# BluetoothModulePCB.net
KiCad netlist of a schematic drawn in EAGLE
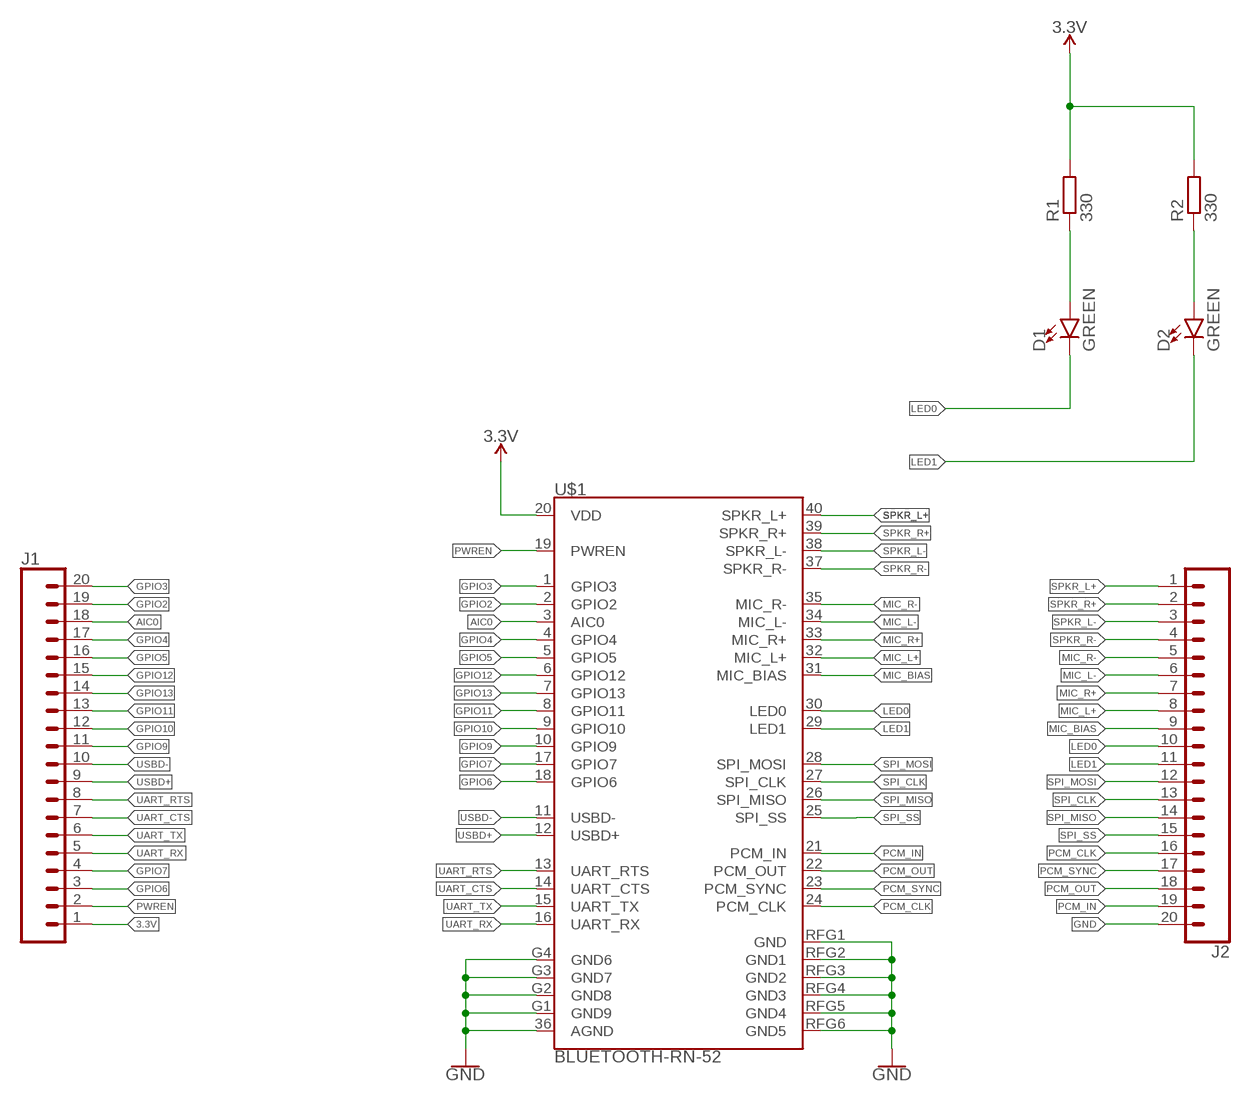
[diagram p0: schematic, sheet 1]

(export (version "E")
  (design (tool "Eeschema 10.0.6"))
  (components
    (comp (ref "D1")
      (value "GREEN")
      (footprint "eagle-import:LED_3MM")
      (libsource (lib "eagle-import") (part "LED3MM"))
    )
    (comp (ref "D2")
      (value "GREEN")
      (footprint "eagle-import:LED_3MM")
      (libsource (lib "eagle-import") (part "LED3MM"))
    )
    (comp (ref "J1")
      (value "CONN_20")
      (footprint "eagle-import:1X20")
      (libsource (lib "eagle-import") (part "CONN_20"))
    )
    (comp (ref "J2")
      (value "CONN_20")
      (footprint "eagle-import:1X20")
      (libsource (lib "eagle-import") (part "CONN_20"))
    )
    (comp (ref "R1")
      (value "330")
      (footprint "eagle-import:0204_7")
      (libsource (lib "eagle-import") (part "R-EU_0204/7"))
    )
    (comp (ref "R2")
      (value "330")
      (footprint "eagle-import:0204_7")
      (libsource (lib "eagle-import") (part "R-EU_0204/7"))
    )
    (comp (ref "U$1")
      (value "BLUETOOTH-RN-52")
      (footprint "eagle-import:RN-52")
      (libsource (lib "eagle-import") (part "BLUETOOTH-RN-52"))
    )
  )
  (nets
    (net (code "1") (name "3.3V") (class "Default")
      (node (ref "J1") (pin "1") (pinfunction "1_1") (pintype "passive"))
      (node (ref "R1") (pin "2") (pinfunction "2_2") (pintype "passive"))
      (node (ref "R2") (pin "2") (pinfunction "2_2") (pintype "passive"))
      (node (ref "U$1") (pin "20") (pinfunction "VDD_20") (pintype "bidirectional"))
    )
    (net (code "2") (name "AIC0") (class "Default")
      (node (ref "J1") (pin "18") (pinfunction "18_18") (pintype "passive"))
      (node (ref "U$1") (pin "3") (pinfunction "AIC0_3") (pintype "bidirectional"))
    )
    (net (code "3") (name "GND") (class "Default")
      (node (ref "J2") (pin "20") (pinfunction "20_20") (pintype "passive"))
      (node (ref "U$1") (pin "36") (pinfunction "AGND_36") (pintype "bidirectional"))
      (node (ref "U$1") (pin "G1") (pinfunction "GND9_G1") (pintype "bidirectional"))
      (node (ref "U$1") (pin "G2") (pinfunction "GND8_G2") (pintype "bidirectional"))
      (node (ref "U$1") (pin "G3") (pinfunction "GND7_G3") (pintype "bidirectional"))
      (node (ref "U$1") (pin "G4") (pinfunction "GND6_G4") (pintype "bidirectional"))
      (node (ref "U$1") (pin "RFG1") (pinfunction "GND_RFG1") (pintype "bidirectional"))
      (node (ref "U$1") (pin "RFG2") (pinfunction "GND1_RFG2") (pintype "bidirectional"))
      (node (ref "U$1") (pin "RFG3") (pinfunction "GND2_RFG3") (pintype "bidirectional"))
      (node (ref "U$1") (pin "RFG4") (pinfunction "GND3_RFG4") (pintype "bidirectional"))
      (node (ref "U$1") (pin "RFG5") (pinfunction "GND4_RFG5") (pintype "bidirectional"))
      (node (ref "U$1") (pin "RFG6") (pinfunction "GND5_RFG6") (pintype "bidirectional"))
    )
    (net (code "4") (name "GPIO2") (class "Default")
      (node (ref "J1") (pin "19") (pinfunction "19_19") (pintype "passive"))
      (node (ref "U$1") (pin "2") (pinfunction "GPIO2_2") (pintype "bidirectional"))
    )
    (net (code "5") (name "GPIO3") (class "Default")
      (node (ref "J1") (pin "20") (pinfunction "20_20") (pintype "passive"))
      (node (ref "U$1") (pin "1") (pinfunction "GPIO3_1") (pintype "bidirectional"))
    )
    (net (code "6") (name "GPIO4") (class "Default")
      (node (ref "J1") (pin "17") (pinfunction "17_17") (pintype "passive"))
      (node (ref "U$1") (pin "4") (pinfunction "GPIO4_4") (pintype "bidirectional"))
    )
    (net (code "7") (name "GPIO5") (class "Default")
      (node (ref "J1") (pin "16") (pinfunction "16_16") (pintype "passive"))
      (node (ref "U$1") (pin "5") (pinfunction "GPIO5_5") (pintype "bidirectional"))
    )
    (net (code "8") (name "GPIO6") (class "Default")
      (node (ref "J1") (pin "3") (pinfunction "3_3") (pintype "passive"))
      (node (ref "U$1") (pin "18") (pinfunction "GPIO6_18") (pintype "bidirectional"))
    )
    (net (code "9") (name "GPIO7") (class "Default")
      (node (ref "J1") (pin "4") (pinfunction "4_4") (pintype "passive"))
      (node (ref "U$1") (pin "17") (pinfunction "GPIO7_17") (pintype "bidirectional"))
    )
    (net (code "10") (name "GPIO9") (class "Default")
      (node (ref "J1") (pin "11") (pinfunction "11_11") (pintype "passive"))
      (node (ref "U$1") (pin "10") (pinfunction "GPIO9_10") (pintype "bidirectional"))
    )
    (net (code "11") (name "GPIO10") (class "Default")
      (node (ref "J1") (pin "12") (pinfunction "12_12") (pintype "passive"))
      (node (ref "U$1") (pin "9") (pinfunction "GPIO10_9") (pintype "bidirectional"))
    )
    (net (code "12") (name "GPIO11") (class "Default")
      (node (ref "J1") (pin "13") (pinfunction "13_13") (pintype "passive"))
      (node (ref "U$1") (pin "8") (pinfunction "GPIO11_8") (pintype "bidirectional"))
    )
    (net (code "13") (name "GPIO12") (class "Default")
      (node (ref "J1") (pin "15") (pinfunction "15_15") (pintype "passive"))
      (node (ref "U$1") (pin "6") (pinfunction "GPIO12_6") (pintype "bidirectional"))
    )
    (net (code "14") (name "GPIO13") (class "Default")
      (node (ref "J1") (pin "14") (pinfunction "14_14") (pintype "passive"))
      (node (ref "U$1") (pin "7") (pinfunction "GPIO13_7") (pintype "bidirectional"))
    )
    (net (code "15") (name "LED0") (class "Default")
      (node (ref "D1") (pin "K") (pinfunction "C_K") (pintype "passive"))
      (node (ref "J2") (pin "10") (pinfunction "10_10") (pintype "passive"))
      (node (ref "U$1") (pin "30") (pinfunction "LED0_30") (pintype "bidirectional"))
    )
    (net (code "16") (name "LED1") (class "Default")
      (node (ref "D2") (pin "K") (pinfunction "C_K") (pintype "passive"))
      (node (ref "J2") (pin "11") (pinfunction "11_11") (pintype "passive"))
      (node (ref "U$1") (pin "29") (pinfunction "LED1_29") (pintype "bidirectional"))
    )
    (net (code "17") (name "MIC_BIAS") (class "Default")
      (node (ref "J2") (pin "9") (pinfunction "9_9") (pintype "passive"))
      (node (ref "U$1") (pin "31") (pinfunction "MIC_BIAS_31") (pintype "bidirectional"))
    )
    (net (code "18") (name "MIC_L+") (class "Default")
      (node (ref "J2") (pin "8") (pinfunction "8_8") (pintype "passive"))
      (node (ref "U$1") (pin "32") (pinfunction "MIC_L+_32") (pintype "bidirectional"))
    )
    (net (code "19") (name "MIC_L-") (class "Default")
      (node (ref "J2") (pin "6") (pinfunction "6_6") (pintype "passive"))
      (node (ref "U$1") (pin "34") (pinfunction "MIC_L-_34") (pintype "bidirectional"))
    )
    (net (code "20") (name "MIC_R+") (class "Default")
      (node (ref "J2") (pin "7") (pinfunction "7_7") (pintype "passive"))
      (node (ref "U$1") (pin "33") (pinfunction "MIC_R+_33") (pintype "bidirectional"))
    )
    (net (code "21") (name "MIC_R-") (class "Default")
      (node (ref "J2") (pin "5") (pinfunction "5_5") (pintype "passive"))
      (node (ref "U$1") (pin "35") (pinfunction "MIC_R-_35") (pintype "bidirectional"))
    )
    (net (code "22") (name "Net-(D1-PadA)") (class "Default")
      (node (ref "D1") (pin "A") (pinfunction "A_A") (pintype "passive"))
      (node (ref "R1") (pin "1") (pinfunction "1_1") (pintype "passive"))
    )
    (net (code "23") (name "Net-(D2-PadA)") (class "Default")
      (node (ref "D2") (pin "A") (pinfunction "A_A") (pintype "passive"))
      (node (ref "R2") (pin "1") (pinfunction "1_1") (pintype "passive"))
    )
    (net (code "24") (name "PCM_CLK") (class "Default")
      (node (ref "J2") (pin "16") (pinfunction "16_16") (pintype "passive"))
      (node (ref "U$1") (pin "24") (pinfunction "PCM_CLK_24") (pintype "bidirectional"))
    )
    (net (code "25") (name "PCM_IN") (class "Default")
      (node (ref "J2") (pin "19") (pinfunction "19_19") (pintype "passive"))
      (node (ref "U$1") (pin "21") (pinfunction "PCM_IN_21") (pintype "bidirectional"))
    )
    (net (code "26") (name "PCM_OUT") (class "Default")
      (node (ref "J2") (pin "18") (pinfunction "18_18") (pintype "passive"))
      (node (ref "U$1") (pin "22") (pinfunction "PCM_OUT_22") (pintype "bidirectional"))
    )
    (net (code "27") (name "PCM_SYNC") (class "Default")
      (node (ref "J2") (pin "17") (pinfunction "17_17") (pintype "passive"))
      (node (ref "U$1") (pin "23") (pinfunction "PCM_SYNC_23") (pintype "bidirectional"))
    )
    (net (code "28") (name "PWREN") (class "Default")
      (node (ref "J1") (pin "2") (pinfunction "2_2") (pintype "passive"))
      (node (ref "U$1") (pin "19") (pinfunction "PWREN_19") (pintype "bidirectional"))
    )
    (net (code "29") (name "SPI_CLK") (class "Default")
      (node (ref "J2") (pin "13") (pinfunction "13_13") (pintype "passive"))
      (node (ref "U$1") (pin "27") (pinfunction "SPI_CLK_27") (pintype "bidirectional"))
    )
    (net (code "30") (name "SPI_MISO") (class "Default")
      (node (ref "J2") (pin "14") (pinfunction "14_14") (pintype "passive"))
      (node (ref "U$1") (pin "26") (pinfunction "SPI_MISO_26") (pintype "bidirectional"))
    )
    (net (code "31") (name "SPI_MOSI") (class "Default")
      (node (ref "J2") (pin "12") (pinfunction "12_12") (pintype "passive"))
      (node (ref "U$1") (pin "28") (pinfunction "SPI_MOSI_28") (pintype "bidirectional"))
    )
    (net (code "32") (name "SPI_SS") (class "Default")
      (node (ref "J2") (pin "15") (pinfunction "15_15") (pintype "passive"))
      (node (ref "U$1") (pin "25") (pinfunction "SPI_SS_25") (pintype "bidirectional"))
    )
    (net (code "33") (name "SPKR_L+") (class "Default")
      (node (ref "J2") (pin "1") (pinfunction "1_1") (pintype "passive"))
      (node (ref "U$1") (pin "40") (pinfunction "SPKR_L+_40") (pintype "bidirectional"))
    )
    (net (code "34") (name "SPKR_L-") (class "Default")
      (node (ref "J2") (pin "3") (pinfunction "3_3") (pintype "passive"))
      (node (ref "U$1") (pin "38") (pinfunction "SPKR_L-_38") (pintype "bidirectional"))
    )
    (net (code "35") (name "SPKR_R+") (class "Default")
      (node (ref "J2") (pin "2") (pinfunction "2_2") (pintype "passive"))
      (node (ref "U$1") (pin "39") (pinfunction "SPKR_R+_39") (pintype "bidirectional"))
    )
    (net (code "36") (name "SPKR_R-") (class "Default")
      (node (ref "J2") (pin "4") (pinfunction "4_4") (pintype "passive"))
      (node (ref "U$1") (pin "37") (pinfunction "SPKR_R-_37") (pintype "bidirectional"))
    )
    (net (code "37") (name "UART_CTS") (class "Default")
      (node (ref "J1") (pin "7") (pinfunction "7_7") (pintype "passive"))
      (node (ref "U$1") (pin "14") (pinfunction "UART_CTS_14") (pintype "bidirectional"))
    )
    (net (code "38") (name "UART_RTS") (class "Default")
      (node (ref "J1") (pin "8") (pinfunction "8_8") (pintype "passive"))
      (node (ref "U$1") (pin "13") (pinfunction "UART_RTS_13") (pintype "bidirectional"))
    )
    (net (code "39") (name "UART_RX") (class "Default")
      (node (ref "J1") (pin "5") (pinfunction "5_5") (pintype "passive"))
      (node (ref "U$1") (pin "16") (pinfunction "UART_RX_16") (pintype "bidirectional"))
    )
    (net (code "40") (name "UART_TX") (class "Default")
      (node (ref "J1") (pin "6") (pinfunction "6_6") (pintype "passive"))
      (node (ref "U$1") (pin "15") (pinfunction "UART_TX_15") (pintype "bidirectional"))
    )
    (net (code "41") (name "USBD+") (class "Default")
      (node (ref "J1") (pin "9") (pinfunction "9_9") (pintype "passive"))
      (node (ref "U$1") (pin "12") (pinfunction "USBD+_12") (pintype "bidirectional"))
    )
    (net (code "42") (name "USBD-") (class "Default")
      (node (ref "J1") (pin "10") (pinfunction "10_10") (pintype "passive"))
      (node (ref "U$1") (pin "11") (pinfunction "USBD-_11") (pintype "bidirectional"))
    )
  )
)
